# Lora_Eval_Module.net
KiCad netlist of a schematic drawn in Altium Designer
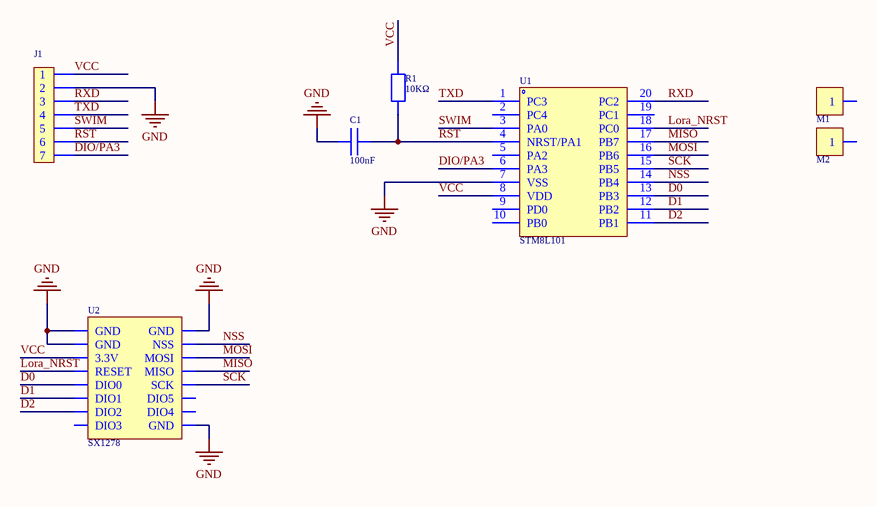
[diagram p0: Lora_Eval_Module.SchDoc]

(export (version "E")
  (design (tool "Eeschema 10.0.6"))
  (components
    (comp (ref "C1")
      (value "100nF")
      (footprint "C0603")
      (libsource (lib "Schematic Library_General") (part "Capacitor_0603"))
    )
    (comp (ref "J1")
      (value "PinHeader_7Pin")
      (footprint "PinHeader_7Pin-2.54mm")
      (libsource (lib "Schematic Library_General") (part "PinHeader_7Pin"))
    )
    (comp (ref "M1")
      (value "PCB Mounting Hole")
      (footprint "PCB Mounting Hole")
      (description "Mounting Hole")
      (libsource (lib "Schematic Library_General") (part "PCB Mounting Hole"))
    )
    (comp (ref "M2")
      (value "PCB Mounting Hole")
      (footprint "PCB Mounting Hole")
      (description "Mounting Hole")
      (libsource (lib "Schematic Library_General") (part "PCB Mounting Hole"))
    )
    (comp (ref "R1")
      (value "10KΩ")
      (footprint "R0805")
      (libsource (lib "Schematic Library_General") (part "Resistor_0805"))
    )
    (comp (ref "U1")
      (value "STM8L101")
      (footprint "TSSOP-20_4.4x6.5mm_P0.65mm")
      (description "4.4x6.5mm_P0.65mm")
      (libsource (lib "Schematic Library_General") (part "STM8L101_TSSOP-20"))
    )
    (comp (ref "U2")
      (value "SX1278")
      (footprint "SX1278_Ra-02-Lora Module_Ai Thinker")
      (description "Footprint from Manufacturer")
      (libsource (lib "Schematic Library_General") (part "SX1278_Ra-02-Lora Module_Ai Thinker"))
    )
  )
  (nets
    (net (code "1") (name "/D0") (class "Default")
      (node (ref "U1") (pin "13") (pinfunction "PB3_13") (pintype "passive"))
      (node (ref "U2") (pin "5") (pinfunction "DIO0_5") (pintype "passive"))
    )
    (net (code "2") (name "/D1") (class "Default")
      (node (ref "U1") (pin "12") (pinfunction "PB2_12") (pintype "passive"))
      (node (ref "U2") (pin "6") (pinfunction "DIO1_6") (pintype "passive"))
    )
    (net (code "3") (name "/D2") (class "Default")
      (node (ref "U1") (pin "11") (pinfunction "PB1_11") (pintype "passive"))
      (node (ref "U2") (pin "7") (pinfunction "DIO2_7") (pintype "passive"))
    )
    (net (code "4") (name "/DIO{slash}PA3") (class "Default")
      (node (ref "J1") (pin "7") (pinfunction "7_7") (pintype "passive"))
      (node (ref "U1") (pin "6") (pinfunction "PA3_6") (pintype "passive"))
    )
    (net (code "5") (name "/Lora_NRST") (class "Default")
      (node (ref "U1") (pin "18") (pinfunction "PC0_18") (pintype "passive"))
      (node (ref "U2") (pin "4") (pinfunction "RESET_4") (pintype "passive"))
    )
    (net (code "6") (name "/MISO") (class "Default")
      (node (ref "U1") (pin "17") (pinfunction "PB7_17") (pintype "passive"))
      (node (ref "U2") (pin "13") (pinfunction "MISO_13") (pintype "passive"))
    )
    (net (code "7") (name "/MOSI") (class "Default")
      (node (ref "U1") (pin "16") (pinfunction "PB6_16") (pintype "passive"))
      (node (ref "U2") (pin "14") (pinfunction "MOSI_14") (pintype "passive"))
    )
    (net (code "8") (name "/NSS") (class "Default")
      (node (ref "U1") (pin "14") (pinfunction "PB4_14") (pintype "passive"))
      (node (ref "U2") (pin "15") (pinfunction "NSS_15") (pintype "passive"))
    )
    (net (code "9") (name "/RST") (class "Default")
      (node (ref "C1") (pin "2") (pintype "passive"))
      (node (ref "J1") (pin "6") (pinfunction "6_6") (pintype "passive"))
      (node (ref "R1") (pin "1") (pintype "passive"))
      (node (ref "U1") (pin "4") (pinfunction "NRST/PA1_4") (pintype "passive"))
    )
    (net (code "10") (name "/RXD") (class "Default")
      (node (ref "J1") (pin "3") (pinfunction "3_3") (pintype "passive"))
      (node (ref "U1") (pin "20") (pinfunction "PC2_20") (pintype "passive"))
    )
    (net (code "11") (name "/SCK") (class "Default")
      (node (ref "U1") (pin "15") (pinfunction "PB5_15") (pintype "passive"))
      (node (ref "U2") (pin "12") (pinfunction "SCK_12") (pintype "passive"))
    )
    (net (code "12") (name "/SWIM") (class "Default")
      (node (ref "J1") (pin "5") (pinfunction "5_5") (pintype "passive"))
      (node (ref "U1") (pin "3") (pinfunction "PA0_3") (pintype "passive"))
    )
    (net (code "13") (name "/TXD") (class "Default")
      (node (ref "J1") (pin "4") (pinfunction "4_4") (pintype "passive"))
      (node (ref "U1") (pin "1") (pinfunction "PC3_1") (pintype "passive"))
    )
    (net (code "14") (name "/VCC") (class "Default")
      (node (ref "J1") (pin "1") (pinfunction "1_1") (pintype "passive"))
      (node (ref "R1") (pin "2") (pintype "passive"))
      (node (ref "U1") (pin "8") (pinfunction "VDD_8") (pintype "passive"))
      (node (ref "U2") (pin "3") (pinfunction "3.3V_3") (pintype "passive"))
    )
    (net (code "15") (name "GND") (class "Default")
      (node (ref "C1") (pin "1") (pintype "passive"))
      (node (ref "J1") (pin "2") (pinfunction "2_2") (pintype "passive"))
      (node (ref "U1") (pin "7") (pinfunction "VSS_7") (pintype "passive"))
      (node (ref "U2") (pin "1") (pinfunction "GND_1") (pintype "passive"))
      (node (ref "U2") (pin "16") (pinfunction "GND_16") (pintype "passive"))
      (node (ref "U2") (pin "2") (pinfunction "GND_2") (pintype "passive"))
      (node (ref "U2") (pin "9") (pinfunction "GND_9") (pintype "passive"))
    )
    (net (code "16") (name "unconnected-(M1-Pad1)") (class "Default")
      (node (ref "M1") (pin "1") (pinfunction "1_1") (pintype "passive"))
    )
    (net (code "17") (name "unconnected-(M2-Pad1)") (class "Default")
      (node (ref "M2") (pin "1") (pinfunction "1_1") (pintype "passive"))
    )
    (net (code "18") (name "unconnected-(U1-PA2-Pad5)") (class "Default")
      (node (ref "U1") (pin "5") (pinfunction "PA2_5") (pintype "passive"))
    )
    (net (code "19") (name "unconnected-(U1-PB0-Pad10)") (class "Default")
      (node (ref "U1") (pin "10") (pinfunction "PB0_10") (pintype "passive"))
    )
    (net (code "20") (name "unconnected-(U1-PC1-Pad19)") (class "Default")
      (node (ref "U1") (pin "19") (pinfunction "PC1_19") (pintype "passive"))
    )
    (net (code "21") (name "unconnected-(U1-PC4-Pad2)") (class "Default")
      (node (ref "U1") (pin "2") (pinfunction "PC4_2") (pintype "passive"))
    )
    (net (code "22") (name "unconnected-(U1-PD0-Pad9)") (class "Default")
      (node (ref "U1") (pin "9") (pinfunction "PD0_9") (pintype "passive"))
    )
    (net (code "23") (name "unconnected-(U2-DIO3-Pad8)") (class "Default")
      (node (ref "U2") (pin "8") (pinfunction "DIO3_8") (pintype "passive"))
    )
    (net (code "24") (name "unconnected-(U2-DIO4-Pad10)") (class "Default")
      (node (ref "U2") (pin "10") (pinfunction "DIO4_10") (pintype "passive"))
    )
    (net (code "25") (name "unconnected-(U2-DIO5-Pad11)") (class "Default")
      (node (ref "U2") (pin "11") (pinfunction "DIO5_11") (pintype "passive"))
    )
  )
)
